# schema_combo_ver_2.net
KiCad netlist of a schematic drawn in Altium Designer
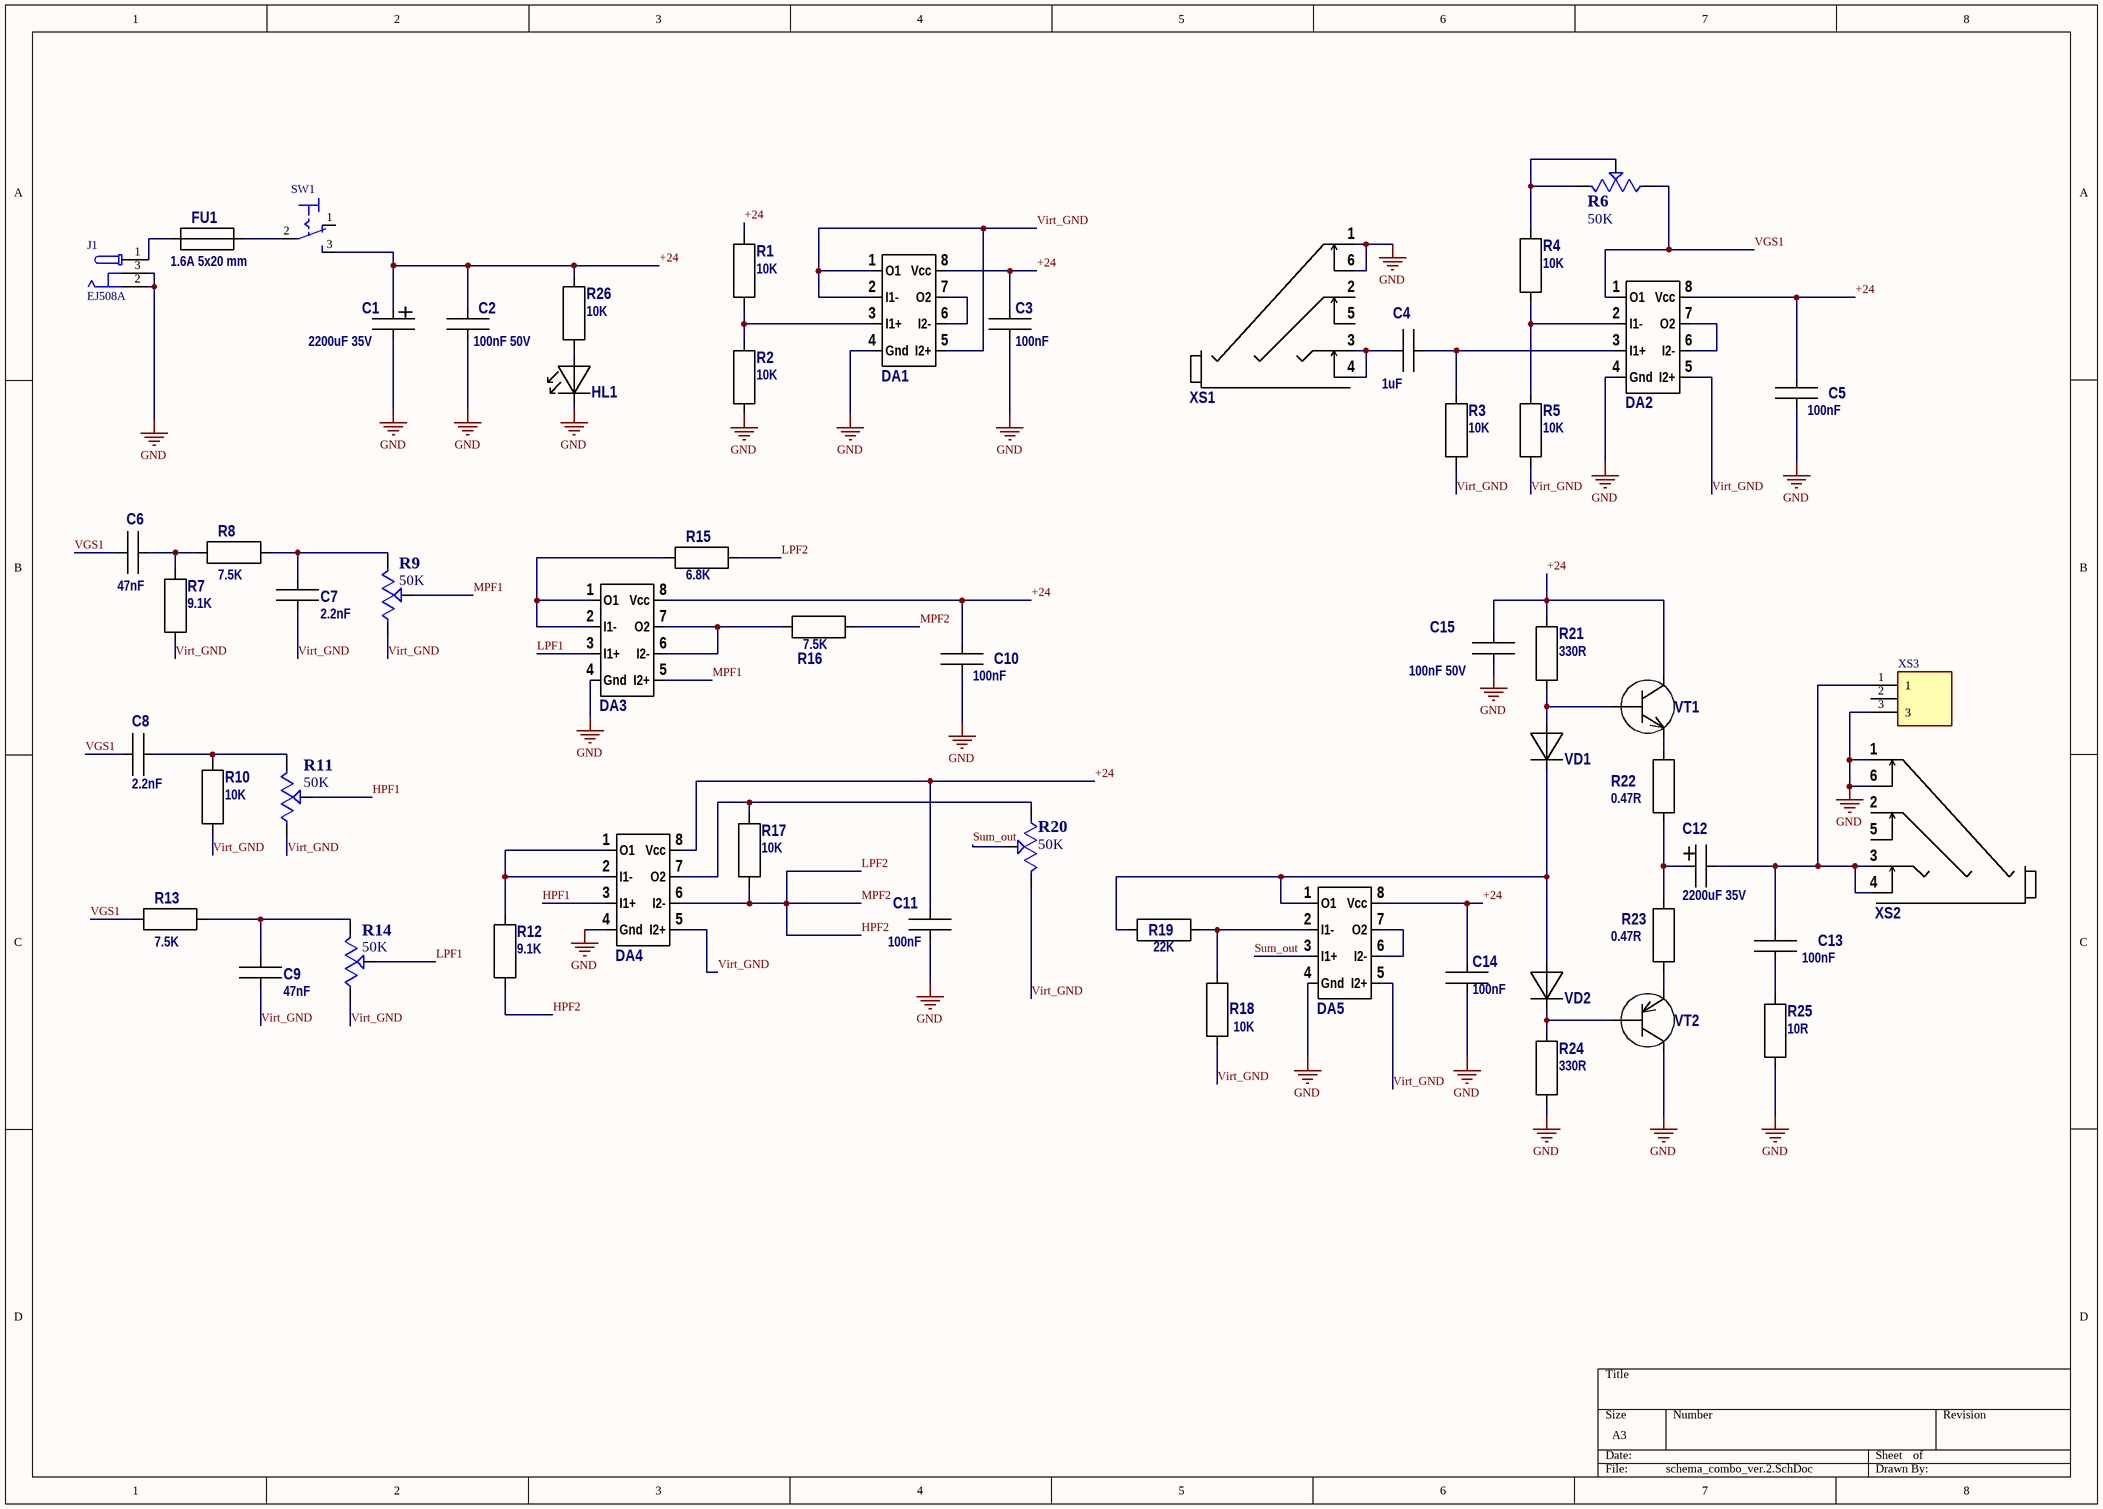
[diagram p0: schema_combo_ver.2.SchDoc]

(export (version "E")
  (design (tool "Eeschema 10.0.6"))
  (components
    (comp (ref "C1")
      (value "2200uF 35V")
      (footprint "capr- 7.5D16.5H35")
      (description "Конденсатор алюминиевый радиальный")
      (libsource (lib "RLC V7.1_BVI") (part "C Al R"))
    )
    (comp (ref "C2")
      (value "100nF 50V")
      (footprint "C__s 5-d 8-t4")
      (description "Конденсатор керамика")
      (libsource (lib "RLC V7.1_BVI") (part "C_Disk"))
    )
    (comp (ref "C3")
      (value "100nF")
      (footprint "cap 1206 3D")
      (description "Конденсатор керамика")
      (libsource (lib "RLC V7.1_BVI") (part "C"))
    )
    (comp (ref "C4")
      (value "1uF")
      (footprint "C__s 5-d 5.5-t4")
      (description "Конденсатор керамика")
      (libsource (lib "RLC V7.1_BVI") (part "C_Disk"))
    )
    (comp (ref "C5")
      (value "100nF")
      (footprint "cap 1206 3D")
      (description "Конденсатор керамика")
      (libsource (lib "RLC V7.1_BVI") (part "C"))
    )
    (comp (ref "C6")
      (value "47nF")
      (footprint "C__s10-d12.4-t4")
      (description "Конденсатор керамика")
      (libsource (lib "RLC V7.1_BVI") (part "C_Disk"))
    )
    (comp (ref "C7")
      (value "2.2nF")
      (footprint "C__s10-d12.4-t4")
      (description "Конденсатор керамика")
      (libsource (lib "RLC V7.1_BVI") (part "C_Disk"))
    )
    (comp (ref "C8")
      (value "2.2nF")
      (footprint "C__s10-d12.4-t4")
      (description "Конденсатор керамика")
      (libsource (lib "RLC V7.1_BVI") (part "C_Disk"))
    )
    (comp (ref "C9")
      (value "47nF")
      (footprint "C__s10-d12.4-t4")
      (description "Конденсатор керамика")
      (libsource (lib "RLC V7.1_BVI") (part "C_Disk"))
    )
    (comp (ref "C10")
      (value "100nF")
      (footprint "cap 1206 3D")
      (description "Конденсатор керамика")
      (libsource (lib "RLC V7.1_BVI") (part "C"))
    )
    (comp (ref "C11")
      (value "100nF")
      (footprint "cap 1206 3D")
      (description "Конденсатор керамика")
      (libsource (lib "RLC V7.1_BVI") (part "C"))
    )
    (comp (ref "C12")
      (value "2200uF 35V")
      (footprint "capr- 7.5D16.5H35")
      (description "Конденсатор алюминиевый радиальный")
      (libsource (lib "RLC V7.1_BVI") (part "C Al R"))
    )
    (comp (ref "C13")
      (value "100nF")
      (footprint "C__s 5-d 7-t4")
      (description "Конденсатор керамика")
      (libsource (lib "RLC V7.1_BVI") (part "C_Disk"))
    )
    (comp (ref "C14")
      (value "100nF")
      (footprint "cap 1206 3D")
      (description "Конденсатор керамика")
      (libsource (lib "RLC V7.1_BVI") (part "C"))
    )
    (comp (ref "C15")
      (value "100nF 50V")
      (footprint "C__s 5-d 8-t4")
      (description "Конденсатор керамика")
      (libsource (lib "RLC V7.1_BVI") (part "C_Disk"))
    )
    (comp (ref "DA1")
      (value "ОУ х 2 (1)")
      (footprint "DIP-8")
      (description "NJM4558/4559  LM158х   LM258х   LM358х   LM2904х  TL072х   NE5532x   SA5532x  и другие")
      (libsource (lib "DA V5.1_BVI") (part "ОУ х 2 (1)"))
    )
    (comp (ref "DA2")
      (value "ОУ х 2 (1)")
      (footprint "DIP-8")
      (description "NJM4558/4559  LM158х   LM258х   LM358х   LM2904х  TL072х   NE5532x   SA5532x  и другие")
      (libsource (lib "DA V5.1_BVI") (part "ОУ х 2 (1)"))
    )
    (comp (ref "DA3")
      (value "ОУ х 2 (1)")
      (footprint "DIP-8")
      (description "NJM4558/4559  LM158х   LM258х   LM358х   LM2904х  TL072х   NE5532x   SA5532x  и другие")
      (libsource (lib "DA V5.1_BVI") (part "ОУ х 2 (1)"))
    )
    (comp (ref "DA4")
      (value "ОУ х 2 (1)")
      (footprint "DIP-8")
      (description "NJM4558/4559  LM158х   LM258х   LM358х   LM2904х  TL072х   NE5532x   SA5532x  и другие")
      (libsource (lib "DA V5.1_BVI") (part "ОУ х 2 (1)"))
    )
    (comp (ref "DA5")
      (value "ОУ х 2 (1)")
      (footprint "DIP-8")
      (description "NJM4558/4559  LM158х   LM258х   LM358х   LM2904х  TL072х   NE5532x   SA5532x  и другие")
      (libsource (lib "DA V5.1_BVI") (part "ОУ х 2 (1)"))
    )
    (comp (ref "FU1")
      (value "1.6A 5x20 mm")
      (footprint "FU_FC-001-N(DH)")
      (description "Предохранитель плавкий с держателем.")
      (libsource (lib "RLC V7.1_BVI") (part "FU + Clip"))
    )
    (comp (ref "HL1")
      (value "???")
      (footprint "СД_D5_8.6_Y кр")
      (description "Св. д. D5 H8.6")
      (libsource (lib "HL Светодиоды_V2.6 BVI") (part "D5  H8.6"))
    )
    (comp (ref "J1")
      (value "EJ508A")
      (footprint "MPD_EJ508A")
      (description "Power Barrel Connector Jack 2.10mm ID _0.083_, 5.50mm OD _0.217_ Through Hole, Right Angle")
      (fields (field (name "MF") "MPD"))
      (libsource (lib "EJ508A") (part "EJ508A"))
    )
    (comp (ref "R1")
      (value "10K")
      (footprint "Res_1206 3D")
      (description "0805 10K")
      (libsource (lib "RLC V7.1_BVI") (part "R"))
    )
    (comp (ref "R2")
      (value "10K")
      (footprint "Res_1206 3D")
      (description "0805 10K")
      (libsource (lib "RLC V7.1_BVI") (part "R"))
    )
    (comp (ref "R3")
      (value "10K")
      (footprint "RES 0.25  L10")
      (description "0805 10K")
      (libsource (lib "RLC V7.1_BVI") (part "R"))
    )
    (comp (ref "R4")
      (value "10K")
      (footprint "RES 0.25  L10")
      (description "R4")
      (libsource (lib "RLC V7.1_BVI") (part "R"))
    )
    (comp (ref "R5")
      (value "10K")
      (footprint "RES 0.25  L10")
      (description "R4")
      (libsource (lib "RLC V7.1_BVI") (part "R"))
    )
    (comp (ref "R6")
      (value "50K")
      (footprint "TRIM_WH148-1A-2-18T-L20")
      (description "16mm Rotary Potentiometers")
      (fields (field (name "MF") "Kls electronics") (field (name "MP") "WH148-1A-2-18T-L20"))
      (libsource (lib "potentiometer") (part "WH148-1A-2-18T-L20"))
    )
    (comp (ref "R7")
      (value "9.1K")
      (footprint "RES 0.25  L10")
      (description "R4")
      (libsource (lib "RLC V7.1_BVI") (part "R"))
    )
    (comp (ref "R8")
      (value "7.5K")
      (footprint "RES 0.25  L10")
      (description "R4")
      (libsource (lib "RLC V7.1_BVI") (part "R"))
    )
    (comp (ref "R9")
      (value "50K")
      (footprint "TRIM_WH148-1A-2-18T-L20")
      (description "16mm Rotary Potentiometers")
      (fields (field (name "MF") "Kls electronics") (field (name "MP") "WH148-1A-2-18T-L20"))
      (libsource (lib "potentiometer") (part "WH148-1A-2-18T-L20"))
    )
    (comp (ref "R10")
      (value "10K")
      (footprint "RES 0.25  L10")
      (description "R4")
      (libsource (lib "RLC V7.1_BVI") (part "R"))
    )
    (comp (ref "R11")
      (value "50K")
      (footprint "TRIM_WH148-1A-2-18T-L20")
      (description "16mm Rotary Potentiometers")
      (fields (field (name "MF") "Kls electronics") (field (name "MP") "WH148-1A-2-18T-L20"))
      (libsource (lib "potentiometer") (part "WH148-1A-2-18T-L20"))
    )
    (comp (ref "R12")
      (value "9.1K")
      (footprint "RES 0.25  L 5")
      (description "R4")
      (libsource (lib "RLC V7.1_BVI") (part "R"))
    )
    (comp (ref "R13")
      (value "7.5K")
      (footprint "RES 0.25  L10")
      (description "R4")
      (libsource (lib "RLC V7.1_BVI") (part "R"))
    )
    (comp (ref "R14")
      (value "50K")
      (footprint "TRIM_WH148-1A-2-18T-L20")
      (description "16mm Rotary Potentiometers")
      (fields (field (name "MF") "Kls electronics") (field (name "MP") "WH148-1A-2-18T-L20"))
      (libsource (lib "potentiometer") (part "WH148-1A-2-18T-L20"))
    )
    (comp (ref "R15")
      (value "6.8K")
      (footprint "RES 0.25  L 3,75")
      (description "R4")
      (libsource (lib "RLC V7.1_BVI") (part "R"))
    )
    (comp (ref "R16")
      (value "7.5K")
      (footprint "RES 0.25  L 3,75")
      (description "R4")
      (libsource (lib "RLC V7.1_BVI") (part "R"))
    )
    (comp (ref "R17")
      (value "10K")
      (footprint "RES 0.25  L 3,75")
      (description "R4")
      (libsource (lib "RLC V7.1_BVI") (part "R"))
    )
    (comp (ref "R18")
      (value "10K")
      (footprint "RES 0.25  L10")
      (description "Резисторы плёночные (SMD; МЛТ; С2-33Н; MP9xxx)")
      (libsource (lib "RLC V7.1_BVI") (part "R"))
    )
    (comp (ref "R19")
      (value "22K")
      (footprint "RES 0.25  L10")
      (description "Резисторы плёночные (SMD; МЛТ; С2-33Н; MP9xxx)")
      (libsource (lib "RLC V7.1_BVI") (part "R"))
    )
    (comp (ref "R20")
      (value "50K")
      (footprint "TRIM_WH148-1A-2-18T-L20")
      (description "16mm Rotary Potentiometers")
      (fields (field (name "MF") "Kls electronics") (field (name "MP") "WH148-1A-2-18T-L20"))
      (libsource (lib "potentiometer") (part "WH148-1A-2-18T-L20"))
    )
    (comp (ref "R21")
      (value "330R")
      (footprint "RES 0.5  L12,5")
      (description "R4")
      (libsource (lib "RLC V7.1_BVI") (part "R"))
    )
    (comp (ref "R22")
      (value "0.47R")
      (footprint "RES 1,0  L15")
      (description "R4")
      (libsource (lib "RLC V7.1_BVI") (part "R"))
    )
    (comp (ref "R23")
      (value "0.47R")
      (footprint "RES 1,0  L15")
      (description "R4")
      (libsource (lib "RLC V7.1_BVI") (part "R"))
    )
    (comp (ref "R24")
      (value "330R")
      (footprint "RES 0.5  L12,5")
      (description "R4")
      (libsource (lib "RLC V7.1_BVI") (part "R"))
    )
    (comp (ref "R25")
      (value "10R")
      (footprint "RES 0.25  L 5")
      (description "R4")
      (libsource (lib "RLC V7.1_BVI") (part "R"))
    )
    (comp (ref "R26")
      (value "10K")
      (footprint "Res_1206 3D")
      (description "0805 10K")
      (libsource (lib "RLC V7.1_BVI") (part "R"))
    )
    (comp (ref "SW1")
      (value "MTS103")
      (footprint "MTS103")
      (description "SW TOG 1P2T 6A ON-OFF-ON MINI SOL THR")
      (fields (field (name "MF") "Not Specified") (field (name "MP") "MTS-103"))
      (libsource (lib "MTS103") (part "MTS103"))
    )
    (comp (ref "VD1")
      (value "Диод.  x1  (2)")
      (footprint "DO-35  (7.5)")
      (description "Диод  одиночный")
      (libsource (lib "VD_VT_V6.3 BVI") (part "Диод.  x1  (2)"))
    )
    (comp (ref "VD2")
      (value "Диод.  x1  (2)")
      (footprint "DO-35  (7.5)")
      (description "Диод  одиночный")
      (libsource (lib "VD_VT_V6.3 BVI") (part "Диод.  x1  (2)"))
    )
    (comp (ref "VT1")
      (value "VT NPN")
      (footprint "TO-220 (Z)")
      (description "Транзистор NPN")
      (libsource (lib "VD_VT_V6.3 BVI") (part "VT NPN"))
    )
    (comp (ref "VT2")
      (value "VT PNP")
      (footprint "TO-220 (Z)")
      (description "Транзистор PNP")
      (libsource (lib "VD_VT_V6.3 BVI") (part "VT PNP"))
    )
    (comp (ref "XS1")
      (value "NYS215")
      (footprint "Гнездо  NYS215")
      (description "Гнездо аудио стерео")
      (libsource (lib "Лампы") (part "NYS 215"))
    )
    (comp (ref "XS2")
      (value "NYS215")
      (footprint "Гнездо  NYS215")
      (description "Гнездо аудио стерео")
      (libsource (lib "Лампы") (part "NYS 215"))
    )
    (comp (ref "XS3")
      (value "MKDSN2,5/3-5.08")
      (footprint "PHOENIX_MKDSN2,5/3-5.08")
      (fields (field (name "MF") "Phoenix Contact"))
      (libsource (lib "MKDSN2_5_3-5.08") (part "MKDSN2,5/3-5.08"))
    )
  )
  (nets
    (net (code "1") (name "/+24") (class "Default")
      (node (ref "C1") (pin "2") (pinfunction "+_2") (pintype "passive"))
      (node (ref "C10") (pin "1") (pintype "passive"))
      (node (ref "C11") (pin "1") (pintype "passive"))
      (node (ref "C14") (pin "1") (pintype "passive"))
      (node (ref "C15") (pin "1") (pintype "passive"))
      (node (ref "C2") (pin "1") (pintype "passive"))
      (node (ref "C3") (pin "1") (pintype "passive"))
      (node (ref "C5") (pin "1") (pintype "passive"))
      (node (ref "DA1") (pin "8") (pinfunction "Vcc_8") (pintype "passive"))
      (node (ref "DA2") (pin "8") (pinfunction "Vcc_8") (pintype "passive"))
      (node (ref "DA3") (pin "8") (pinfunction "Vcc_8") (pintype "passive"))
      (node (ref "DA4") (pin "8") (pinfunction "Vcc_8") (pintype "passive"))
      (node (ref "DA5") (pin "8") (pinfunction "Vcc_8") (pintype "passive"))
      (node (ref "R1") (pin "2") (pintype "passive"))
      (node (ref "R21") (pin "2") (pintype "passive"))
      (node (ref "R26") (pin "2") (pintype "passive"))
      (node (ref "SW1") (pin "3") (pinfunction "S_3") (pintype "passive"))
      (node (ref "VT1") (pin "2") (pinfunction "C_2") (pintype "passive"))
    )
    (net (code "2") (name "/HPF1") (class "Default")
      (node (ref "DA4") (pin "3") (pinfunction "I1+_3") (pintype "passive"))
      (node (ref "R11") (pin "2") (pinfunction "2_2") (pintype "passive"))
    )
    (net (code "3") (name "/HPF2") (class "Default")
      (node (ref "DA4") (pin "6") (pinfunction "I2-_6") (pintype "passive"))
      (node (ref "R12") (pin "1") (pintype "passive"))
      (node (ref "R15") (pin "2") (pintype "passive"))
      (node (ref "R16") (pin "2") (pintype "passive"))
      (node (ref "R17") (pin "1") (pintype "passive"))
    )
    (net (code "4") (name "/LPF1") (class "Default")
      (node (ref "DA3") (pin "3") (pinfunction "I1+_3") (pintype "passive"))
      (node (ref "R14") (pin "2") (pinfunction "2_2") (pintype "passive"))
    )
    (net (code "5") (name "/MPF1") (class "Default")
      (node (ref "DA3") (pin "5") (pinfunction "I2+_5") (pintype "passive"))
      (node (ref "R9") (pin "2") (pinfunction "2_2") (pintype "passive"))
    )
    (net (code "6") (name "/Sum_out") (class "Default")
      (node (ref "DA5") (pin "3") (pinfunction "I1+_3") (pintype "passive"))
      (node (ref "R20") (pin "2") (pinfunction "2_2") (pintype "passive"))
    )
    (net (code "7") (name "/VGS1") (class "Default")
      (node (ref "C6") (pin "1") (pintype "passive"))
      (node (ref "C8") (pin "2") (pintype "passive"))
      (node (ref "DA2") (pin "1") (pinfunction "O1_1") (pintype "passive"))
      (node (ref "R13") (pin "1") (pintype "passive"))
      (node (ref "R6") (pin "1") (pinfunction "1_1") (pintype "passive"))
    )
    (net (code "8") (name "/Virt_GND") (class "Default")
      (node (ref "C7") (pin "1") (pintype "passive"))
      (node (ref "C9") (pin "1") (pintype "passive"))
      (node (ref "DA1") (pin "1") (pinfunction "O1_1") (pintype "passive"))
      (node (ref "DA1") (pin "2") (pinfunction "I1-_2") (pintype "passive"))
      (node (ref "DA1") (pin "5") (pinfunction "I2+_5") (pintype "passive"))
      (node (ref "DA2") (pin "5") (pinfunction "I2+_5") (pintype "passive"))
      (node (ref "DA4") (pin "5") (pinfunction "I2+_5") (pintype "passive"))
      (node (ref "DA5") (pin "5") (pinfunction "I2+_5") (pintype "passive"))
      (node (ref "R10") (pin "2") (pintype "passive"))
      (node (ref "R11") (pin "1") (pinfunction "1_1") (pintype "passive"))
      (node (ref "R14") (pin "1") (pinfunction "1_1") (pintype "passive"))
      (node (ref "R18") (pin "1") (pintype "passive"))
      (node (ref "R20") (pin "1") (pinfunction "1_1") (pintype "passive"))
      (node (ref "R3") (pin "1") (pintype "passive"))
      (node (ref "R5") (pin "2") (pintype "passive"))
      (node (ref "R7") (pin "1") (pintype "passive"))
      (node (ref "R9") (pin "1") (pinfunction "1_1") (pintype "passive"))
    )
    (net (code "9") (name "GND") (class "Default")
      (node (ref "C1") (pin "1") (pinfunction "-_1") (pintype "passive"))
      (node (ref "C10") (pin "2") (pintype "passive"))
      (node (ref "C11") (pin "2") (pintype "passive"))
      (node (ref "C14") (pin "2") (pintype "passive"))
      (node (ref "C15") (pin "2") (pintype "passive"))
      (node (ref "C2") (pin "2") (pintype "passive"))
      (node (ref "C3") (pin "2") (pintype "passive"))
      (node (ref "C5") (pin "2") (pintype "passive"))
      (node (ref "DA1") (pin "4") (pinfunction "Gnd_4") (pintype "passive"))
      (node (ref "DA2") (pin "4") (pinfunction "Gnd_4") (pintype "passive"))
      (node (ref "DA3") (pin "4") (pinfunction "Gnd_4") (pintype "passive"))
      (node (ref "DA4") (pin "4") (pinfunction "Gnd_4") (pintype "passive"))
      (node (ref "DA5") (pin "4") (pinfunction "Gnd_4") (pintype "passive"))
      (node (ref "HL1") (pin "1") (pinfunction "K_1") (pintype "passive"))
      (node (ref "J1") (pin "2") (pinfunction "2_2") (pintype "passive"))
      (node (ref "J1") (pin "3") (pinfunction "3_3") (pintype "passive"))
      (node (ref "R2") (pin "1") (pintype "passive"))
      (node (ref "R24") (pin "1") (pintype "passive"))
      (node (ref "R25") (pin "1") (pintype "passive"))
      (node (ref "VT2") (pin "2") (pinfunction "C_2") (pintype "passive"))
      (node (ref "XS1") (pin "1") (pintype "passive"))
      (node (ref "XS1") (pin "6") (pintype "passive"))
      (node (ref "XS2") (pin "1") (pintype "passive"))
      (node (ref "XS2") (pin "6") (pintype "passive"))
      (node (ref "XS3") (pin "3") (pinfunction "3_3") (pintype "passive"))
    )
    (net (code "10") (name "Net-(C4-Pad2)") (class "Default")
      (node (ref "C4") (pin "2") (pintype "passive"))
      (node (ref "XS1") (pin "3") (pintype "passive"))
      (node (ref "XS1") (pin "4") (pintype "passive"))
    )
    (net (code "11") (name "Net-(C6-Pad2)") (class "Default")
      (node (ref "C6") (pin "2") (pintype "passive"))
      (node (ref "R7") (pin "2") (pintype "passive"))
      (node (ref "R8") (pin "1") (pintype "passive"))
    )
    (net (code "12") (name "Net-(C7-Pad2)") (class "Default")
      (node (ref "C7") (pin "2") (pintype "passive"))
      (node (ref "R8") (pin "2") (pintype "passive"))
      (node (ref "R9") (pin "3") (pinfunction "3_3") (pintype "passive"))
    )
    (net (code "13") (name "Net-(C8-Pad1)") (class "Default")
      (node (ref "C8") (pin "1") (pintype "passive"))
      (node (ref "R10") (pin "1") (pintype "passive"))
      (node (ref "R11") (pin "3") (pinfunction "3_3") (pintype "passive"))
    )
    (net (code "14") (name "Net-(C9-Pad2)") (class "Default")
      (node (ref "C9") (pin "2") (pintype "passive"))
      (node (ref "R13") (pin "2") (pintype "passive"))
      (node (ref "R14") (pin "3") (pinfunction "3_3") (pintype "passive"))
    )
    (net (code "15") (name "Net-(C12-+)") (class "Default")
      (node (ref "C12") (pin "2") (pinfunction "+_2") (pintype "passive"))
      (node (ref "R22") (pin "2") (pintype "passive"))
      (node (ref "R23") (pin "2") (pintype "passive"))
    )
    (net (code "16") (name "Net-(C12--)") (class "Default")
      (node (ref "C12") (pin "1") (pinfunction "-_1") (pintype "passive"))
      (node (ref "C13") (pin "1") (pintype "passive"))
      (node (ref "XS2") (pin "3") (pintype "passive"))
      (node (ref "XS2") (pin "4") (pintype "passive"))
      (node (ref "XS3") (pin "1") (pinfunction "1_1") (pintype "passive"))
    )
    (net (code "17") (name "Net-(C13-Pad2)") (class "Default")
      (node (ref "C13") (pin "2") (pintype "passive"))
      (node (ref "R25") (pin "2") (pintype "passive"))
    )
    (net (code "18") (name "Net-(DA1-I1+)") (class "Default")
      (node (ref "DA1") (pin "3") (pinfunction "I1+_3") (pintype "passive"))
      (node (ref "R1") (pin "1") (pintype "passive"))
      (node (ref "R2") (pin "2") (pintype "passive"))
    )
    (net (code "19") (name "Net-(DA1-I2-)") (class "Default")
      (node (ref "DA1") (pin "6") (pinfunction "I2-_6") (pintype "passive"))
      (node (ref "DA1") (pin "7") (pinfunction "O2_7") (pintype "passive"))
    )
    (net (code "20") (name "Net-(DA2-I1+)") (class "Default")
      (node (ref "C4") (pin "1") (pintype "passive"))
      (node (ref "DA2") (pin "3") (pinfunction "I1+_3") (pintype "passive"))
      (node (ref "R3") (pin "2") (pintype "passive"))
    )
    (net (code "21") (name "Net-(DA2-I1-)") (class "Default")
      (node (ref "DA2") (pin "2") (pinfunction "I1-_2") (pintype "passive"))
      (node (ref "R4") (pin "2") (pintype "passive"))
      (node (ref "R5") (pin "1") (pintype "passive"))
    )
    (net (code "22") (name "Net-(DA2-I2-)") (class "Default")
      (node (ref "DA2") (pin "6") (pinfunction "I2-_6") (pintype "passive"))
      (node (ref "DA2") (pin "7") (pinfunction "O2_7") (pintype "passive"))
    )
    (net (code "23") (name "Net-(DA3-I1-)") (class "Default")
      (node (ref "DA3") (pin "1") (pinfunction "O1_1") (pintype "passive"))
      (node (ref "DA3") (pin "2") (pinfunction "I1-_2") (pintype "passive"))
      (node (ref "R15") (pin "1") (pintype "passive"))
    )
    (net (code "24") (name "Net-(DA3-I2-)") (class "Default")
      (node (ref "DA3") (pin "6") (pinfunction "I2-_6") (pintype "passive"))
      (node (ref "DA3") (pin "7") (pinfunction "O2_7") (pintype "passive"))
      (node (ref "R16") (pin "1") (pintype "passive"))
    )
    (net (code "25") (name "Net-(DA4-I1-)") (class "Default")
      (node (ref "DA4") (pin "1") (pinfunction "O1_1") (pintype "passive"))
      (node (ref "DA4") (pin "2") (pinfunction "I1-_2") (pintype "passive"))
      (node (ref "R12") (pin "2") (pintype "passive"))
    )
    (net (code "26") (name "Net-(DA4-O2)") (class "Default")
      (node (ref "DA4") (pin "7") (pinfunction "O2_7") (pintype "passive"))
      (node (ref "R17") (pin "2") (pintype "passive"))
      (node (ref "R20") (pin "3") (pinfunction "3_3") (pintype "passive"))
    )
    (net (code "27") (name "Net-(DA5-I1-)") (class "Default")
      (node (ref "DA5") (pin "2") (pinfunction "I1-_2") (pintype "passive"))
      (node (ref "R18") (pin "2") (pintype "passive"))
      (node (ref "R19") (pin "2") (pintype "passive"))
    )
    (net (code "28") (name "Net-(DA5-I2-)") (class "Default")
      (node (ref "DA5") (pin "6") (pinfunction "I2-_6") (pintype "passive"))
      (node (ref "DA5") (pin "7") (pinfunction "O2_7") (pintype "passive"))
    )
    (net (code "29") (name "Net-(DA5-O1)") (class "Default")
      (node (ref "DA5") (pin "1") (pinfunction "O1_1") (pintype "passive"))
      (node (ref "R19") (pin "1") (pintype "passive"))
      (node (ref "VD1") (pin "1") (pinfunction "K_1") (pintype "passive"))
      (node (ref "VD2") (pin "2") (pinfunction "A_2") (pintype "passive"))
    )
    (net (code "30") (name "Net-(FU1-Pad1)") (class "Default")
      (node (ref "FU1") (pin "1") (pintype "passive"))
      (node (ref "J1") (pin "1") (pinfunction "1_1") (pintype "passive"))
    )
    (net (code "31") (name "Net-(HL1-A)") (class "Default")
      (node (ref "HL1") (pin "2") (pinfunction "A_2") (pintype "passive"))
      (node (ref "R26") (pin "1") (pintype "passive"))
    )
    (net (code "32") (name "Net-(R4-Pad1)") (class "Default")
      (node (ref "R4") (pin "1") (pintype "passive"))
      (node (ref "R6") (pin "2") (pinfunction "2_2") (pintype "passive"))
      (node (ref "R6") (pin "3") (pinfunction "3_3") (pintype "passive"))
    )
    (net (code "33") (name "Net-(SW1-P)") (class "Default")
      (node (ref "FU1") (pin "2") (pintype "passive"))
      (node (ref "SW1") (pin "2") (pinfunction "P_2") (pintype "passive"))
    )
    (net (code "34") (name "Net-(VD1-A)") (class "Default")
      (node (ref "R21") (pin "1") (pintype "passive"))
      (node (ref "VD1") (pin "2") (pinfunction "A_2") (pintype "passive"))
      (node (ref "VT1") (pin "1") (pinfunction "B_1") (pintype "passive"))
    )
    (net (code "35") (name "Net-(VD2-K)") (class "Default")
      (node (ref "R24") (pin "2") (pintype "passive"))
      (node (ref "VD2") (pin "1") (pinfunction "K_1") (pintype "passive"))
      (node (ref "VT2") (pin "1") (pinfunction "B_1") (pintype "passive"))
    )
    (net (code "36") (name "Net-(VT1-E)") (class "Default")
      (node (ref "R22") (pin "1") (pintype "passive"))
      (node (ref "VT1") (pin "3") (pinfunction "E_3") (pintype "passive"))
    )
    (net (code "37") (name "Net-(VT2-E)") (class "Default")
      (node (ref "R23") (pin "1") (pintype "passive"))
      (node (ref "VT2") (pin "3") (pinfunction "E_3") (pintype "passive"))
    )
    (net (code "38") (name "unconnected-(SW1-O-Pad1)") (class "Default")
      (node (ref "SW1") (pin "1") (pinfunction "O_1") (pintype "passive"))
    )
    (net (code "39") (name "unconnected-(XS1-Pad2)") (class "Default")
      (node (ref "XS1") (pin "2") (pintype "passive"))
    )
    (net (code "40") (name "unconnected-(XS1-Pad5)") (class "Default")
      (node (ref "XS1") (pin "5") (pintype "passive"))
    )
    (net (code "41") (name "unconnected-(XS2-Pad2)") (class "Default")
      (node (ref "XS2") (pin "2") (pintype "passive"))
    )
    (net (code "42") (name "unconnected-(XS2-Pad5)") (class "Default")
      (node (ref "XS2") (pin "5") (pintype "passive"))
    )
    (net (code "43") (name "unconnected-(XS3-Pad2)") (class "Default")
      (node (ref "XS3") (pin "2") (pinfunction "2_2") (pintype "passive"))
    )
  )
)
